# Filter_Capacitors_-_I2C.net
KiCad netlist of a schematic drawn in Altium Designer
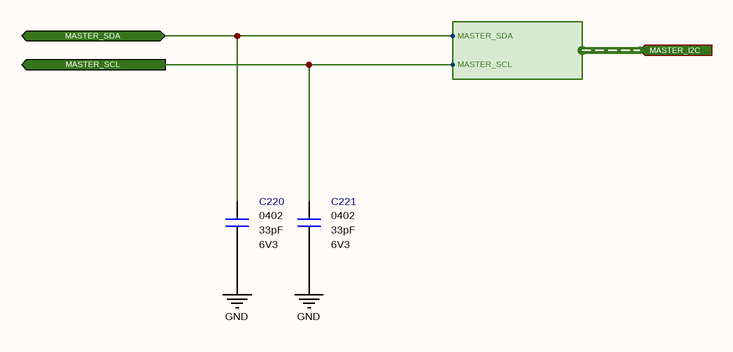
[diagram p0: Filter Capacitors - I2C.SchDoc]

(export (version "E")
  (design (tool "Eeschema 10.0.6"))
  (components
    (comp (ref "C220")
      (value "33pF")
      (footprint "CAPACITOR_0402")
      (description "Capacitor - 33pF [0402] (Ceramic)")
      (fields
        (field (name "TOLERANCE") "10%")
        (field (name "CASE") "0402")
        (field (name "VOLTAGE") "6V3")
        (field (name "MANUFACTURER PART NUMBER") "C0402C330J9RACAUTO")
      )
      (libsource (lib "Ovoo_Library") (part "Capacitor - 33pF [0402-6V3]"))
    )
    (comp (ref "C221")
      (value "33pF")
      (footprint "CAPACITOR_0402")
      (description "Capacitor - 33pF [0402] (Ceramic)")
      (fields
        (field (name "TOLERANCE") "10%")
        (field (name "CASE") "0402")
        (field (name "VOLTAGE") "6V3")
        (field (name "MANUFACTURER PART NUMBER") "C0402C330J9RACAUTO")
      )
      (libsource (lib "Ovoo_Library") (part "Capacitor - 33pF [0402-6V3]"))
    )
  )
  (nets
    (net (code "2") (name "/MASTER_SCL") (class "Default")
      (node (ref "C221") (pin "2") (pinfunction "2_2") (pintype "passive"))
    )
    (net (code "3") (name "/MASTER_SDA") (class "Default")
      (node (ref "C220") (pin "2") (pinfunction "2_2") (pintype "passive"))
    )
    (net (code "5") (name "GND") (class "Default")
      (node (ref "C220") (pin "1") (pinfunction "1_1") (pintype "passive"))
      (node (ref "C221") (pin "1") (pinfunction "1_1") (pintype "passive"))
    )
  )
)
